# PROB_S7CAS_PHY.net
KiCad netlist of a schematic drawn in Altium Designer
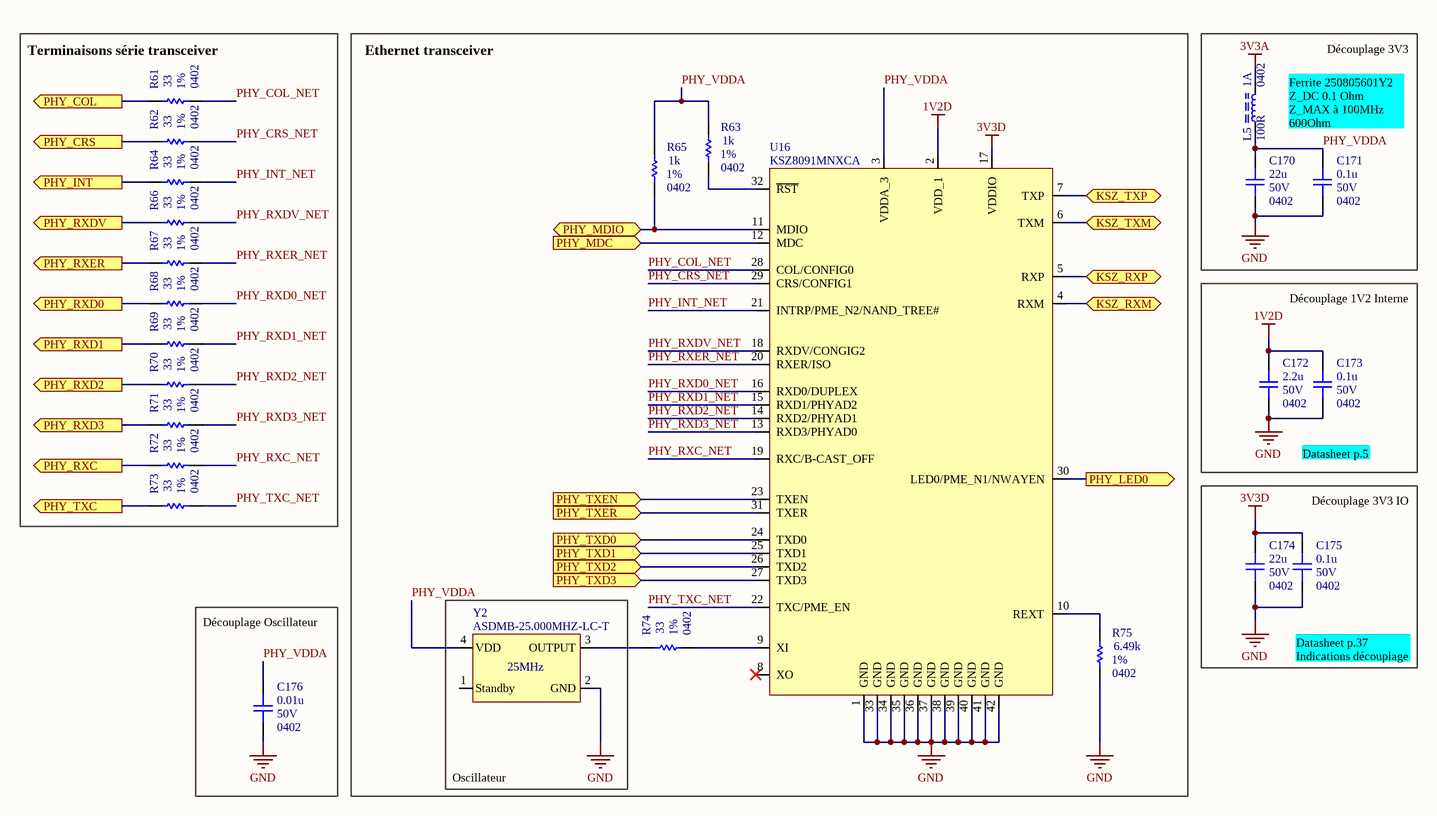
[diagram p0: PROB_S7CAS_PHY.SchDoc]

(export (version "E")
  (design (tool "Eeschema 10.0.6"))
  (components
    (comp (ref "C170")
      (value "22u")
      (footprint "CAP_0402")
      (description "CAP - 0402")
      (fields
        (field (name "VOLTAGE") "50V")
        (field (name "PACKAGE") "0402")
        (field (name "CREATEDBY") "Jonathan Bouchard")
      )
      (libsource (lib "S7CAS_LIB2021") (part "CAP - 0402"))
    )
    (comp (ref "C171")
      (value "0.1u")
      (footprint "CAP_0402")
      (description "CAP - 0402")
      (fields
        (field (name "VOLTAGE") "50V")
        (field (name "PACKAGE") "0402")
        (field (name "CREATEDBY") "Jonathan Bouchard")
      )
      (libsource (lib "S7CAS_LIB2021") (part "CAP - 0402"))
    )
    (comp (ref "C172")
      (value "2.2u")
      (footprint "CAP_0402")
      (description "CAP - 0402")
      (fields
        (field (name "VOLTAGE") "50V")
        (field (name "PACKAGE") "0402")
        (field (name "CREATEDBY") "Jonathan Bouchard")
      )
      (libsource (lib "S7CAS_LIB2021") (part "CAP - 0402"))
    )
    (comp (ref "C173")
      (value "0.1u")
      (footprint "CAP_0402")
      (description "CAP - 0402")
      (fields
        (field (name "VOLTAGE") "50V")
        (field (name "PACKAGE") "0402")
        (field (name "CREATEDBY") "Jonathan Bouchard")
      )
      (libsource (lib "S7CAS_LIB2021") (part "CAP - 0402"))
    )
    (comp (ref "C174")
      (value "22u")
      (footprint "CAP_0402")
      (description "CAP - 0402")
      (fields
        (field (name "VOLTAGE") "50V")
        (field (name "PACKAGE") "0402")
        (field (name "CREATEDBY") "Jonathan Bouchard")
      )
      (libsource (lib "S7CAS_LIB2021") (part "CAP - 0402"))
    )
    (comp (ref "C175")
      (value "0.1u")
      (footprint "CAP_0402")
      (description "CAP - 0402")
      (fields
        (field (name "VOLTAGE") "50V")
        (field (name "PACKAGE") "0402")
        (field (name "CREATEDBY") "Jonathan Bouchard")
      )
      (libsource (lib "S7CAS_LIB2021") (part "CAP - 0402"))
    )
    (comp (ref "C176")
      (value "0.01u")
      (footprint "CAP_0402")
      (description "CAP - 0402")
      (fields
        (field (name "VOLTAGE") "50V")
        (field (name "PACKAGE") "0402")
        (field (name "CREATEDBY") "Jonathan Bouchard")
      )
      (libsource (lib "S7CAS_LIB2021") (part "CAP - 0402"))
    )
    (comp (ref "L5")
      (value "100R")
      (footprint "FER_0402")
      (description "FER - 0402")
      (fields
        (field (name "CURRENT") "1A")
        (field (name "PACKAGE") "0402")
        (field (name "CREATEDBY") "Jonathan Bouchard")
      )
      (libsource (lib "S7CAS_LIB2021") (part "FER - 0402"))
    )
    (comp (ref "R61")
      (value "33")
      (footprint "RES_0402")
      (description "RES - 0402")
      (fields
        (field (name "VOLTAGE") "50V")
        (field (name "POWER") "1/16W")
        (field (name "PACKAGE") "0402")
        (field (name "PRECISION") "1%")
        (field (name "CREATEDBY") "Jonathan Bouchard")
      )
      (libsource (lib "S7CAS_LIB2021") (part "RES - 0402"))
    )
    (comp (ref "R62")
      (value "33")
      (footprint "RES_0402")
      (description "RES - 0402")
      (fields
        (field (name "VOLTAGE") "50V")
        (field (name "POWER") "1/16W")
        (field (name "PACKAGE") "0402")
        (field (name "PRECISION") "1%")
        (field (name "CREATEDBY") "Jonathan Bouchard")
      )
      (libsource (lib "S7CAS_LIB2021") (part "RES - 0402"))
    )
    (comp (ref "R63")
      (value "1k")
      (footprint "RES_0402")
      (description "RES - 0402")
      (fields
        (field (name "VOLTAGE") "50V")
        (field (name "POWER") "1/16W")
        (field (name "PACKAGE") "0402")
        (field (name "PRECISION") "1%")
        (field (name "CREATEDBY") "Jonathan Bouchard")
      )
      (libsource (lib "S7CAS_LIB2021") (part "RES - 0402"))
    )
    (comp (ref "R64")
      (value "33")
      (footprint "RES_0402")
      (description "RES - 0402")
      (fields
        (field (name "VOLTAGE") "50V")
        (field (name "POWER") "1/16W")
        (field (name "PACKAGE") "0402")
        (field (name "PRECISION") "1%")
        (field (name "CREATEDBY") "Jonathan Bouchard")
      )
      (libsource (lib "S7CAS_LIB2021") (part "RES - 0402"))
    )
    (comp (ref "R65")
      (value "1k")
      (footprint "RES_0402")
      (description "RES - 0402")
      (fields
        (field (name "VOLTAGE") "50V")
        (field (name "POWER") "1/16W")
        (field (name "PACKAGE") "0402")
        (field (name "PRECISION") "1%")
        (field (name "CREATEDBY") "Jonathan Bouchard")
      )
      (libsource (lib "S7CAS_LIB2021") (part "RES - 0402"))
    )
    (comp (ref "R66")
      (value "33")
      (footprint "RES_0402")
      (description "RES - 0402")
      (fields
        (field (name "VOLTAGE") "50V")
        (field (name "POWER") "1/16W")
        (field (name "PACKAGE") "0402")
        (field (name "PRECISION") "1%")
        (field (name "CREATEDBY") "Jonathan Bouchard")
      )
      (libsource (lib "S7CAS_LIB2021") (part "RES - 0402"))
    )
    (comp (ref "R67")
      (value "33")
      (footprint "RES_0402")
      (description "RES - 0402")
      (fields
        (field (name "VOLTAGE") "50V")
        (field (name "POWER") "1/16W")
        (field (name "PACKAGE") "0402")
        (field (name "PRECISION") "1%")
        (field (name "CREATEDBY") "Jonathan Bouchard")
      )
      (libsource (lib "S7CAS_LIB2021") (part "RES - 0402"))
    )
    (comp (ref "R68")
      (value "33")
      (footprint "RES_0402")
      (description "RES - 0402")
      (fields
        (field (name "VOLTAGE") "50V")
        (field (name "POWER") "1/16W")
        (field (name "PACKAGE") "0402")
        (field (name "PRECISION") "1%")
        (field (name "CREATEDBY") "Jonathan Bouchard")
      )
      (libsource (lib "S7CAS_LIB2021") (part "RES - 0402"))
    )
    (comp (ref "R69")
      (value "33")
      (footprint "RES_0402")
      (description "RES - 0402")
      (fields
        (field (name "VOLTAGE") "50V")
        (field (name "POWER") "1/16W")
        (field (name "PACKAGE") "0402")
        (field (name "PRECISION") "1%")
        (field (name "CREATEDBY") "Jonathan Bouchard")
      )
      (libsource (lib "S7CAS_LIB2021") (part "RES - 0402"))
    )
    (comp (ref "R70")
      (value "33")
      (footprint "RES_0402")
      (description "RES - 0402")
      (fields
        (field (name "VOLTAGE") "50V")
        (field (name "POWER") "1/16W")
        (field (name "PACKAGE") "0402")
        (field (name "PRECISION") "1%")
        (field (name "CREATEDBY") "Jonathan Bouchard")
      )
      (libsource (lib "S7CAS_LIB2021") (part "RES - 0402"))
    )
    (comp (ref "R71")
      (value "33")
      (footprint "RES_0402")
      (description "RES - 0402")
      (fields
        (field (name "VOLTAGE") "50V")
        (field (name "POWER") "1/16W")
        (field (name "PACKAGE") "0402")
        (field (name "PRECISION") "1%")
        (field (name "CREATEDBY") "Jonathan Bouchard")
      )
      (libsource (lib "S7CAS_LIB2021") (part "RES - 0402"))
    )
    (comp (ref "R72")
      (value "33")
      (footprint "RES_0402")
      (description "RES - 0402")
      (fields
        (field (name "VOLTAGE") "50V")
        (field (name "POWER") "1/16W")
        (field (name "PACKAGE") "0402")
        (field (name "PRECISION") "1%")
        (field (name "CREATEDBY") "Jonathan Bouchard")
      )
      (libsource (lib "S7CAS_LIB2021") (part "RES - 0402"))
    )
    (comp (ref "R73")
      (value "33")
      (footprint "RES_0402")
      (description "RES - 0402")
      (fields
        (field (name "VOLTAGE") "50V")
        (field (name "POWER") "1/16W")
        (field (name "PACKAGE") "0402")
        (field (name "PRECISION") "1%")
        (field (name "CREATEDBY") "Jonathan Bouchard")
      )
      (libsource (lib "S7CAS_LIB2021") (part "RES - 0402"))
    )
    (comp (ref "R74")
      (value "33")
      (footprint "RES_0402")
      (description "RES - 0402")
      (fields
        (field (name "VOLTAGE") "50V")
        (field (name "POWER") "1/16W")
        (field (name "PACKAGE") "0402")
        (field (name "PRECISION") "1%")
        (field (name "CREATEDBY") "Jonathan Bouchard")
      )
      (libsource (lib "S7CAS_LIB2021") (part "RES - 0402"))
    )
    (comp (ref "R75")
      (value "6.49k")
      (footprint "RES_0402")
      (description "RES - 0402")
      (fields
        (field (name "VOLTAGE") "50V")
        (field (name "POWER") "1/16W")
        (field (name "PACKAGE") "0402")
        (field (name "PRECISION") "1%")
        (field (name "CREATEDBY") "Jonathan Bouchard")
      )
      (libsource (lib "S7CAS_LIB2021") (part "RES - 0402"))
    )
    (comp (ref "U16")
      (value "KSZ8091MNXCA")
      (footprint "COM_ETH_PHY_KSZ8091MNXCA")
      (description "COM - ETHERNET PHY 10/100 - QFN-32")
      (fields
        (field (name "VOLTAGE") "1.8V, 2.5V, 3.3V")
        (field (name "MFG") "Micrel")
        (field (name "CREATEDBY") "Jonathan Bouchard")
      )
      (libsource (lib "S7CAS_LIB2021") (part "COM_ETH_PHY_KSZ8091MNXCA"))
    )
    (comp (ref "Y2")
      (value "ASDMB-25.000MHZ-LC-T")
      (footprint "OSC_ASDMB-25.000MHZ-LC-T")
      (description "OSC - 25MHz XO (Standard) LVCMOS - 4-SMD, No Lead")
      (fields
        (field (name "TOLERANCE") "±50ppm")
        (field (name "CREATEDBY/DATE") "Joël Lemay 2019-03-29")
        (field (name "VERIFIEDBY") "C. Paulin - 29 mai 2019")
      )
      (libsource (lib "S7CAS_LIB2021") (part "OSC_ASDMB-25.000MHZ-LC-T"))
    )
  )
  (nets
    (net (code "1") (name "/KSZ_RXM") (class "Default")
      (node (ref "U16") (pin "4") (pinfunction "RXM_4") (pintype "passive"))
    )
    (net (code "2") (name "/KSZ_RXP") (class "Default")
      (node (ref "U16") (pin "5") (pinfunction "RXP_5") (pintype "passive"))
    )
    (net (code "3") (name "/KSZ_TXM") (class "Default")
      (node (ref "U16") (pin "6") (pinfunction "TXM_6") (pintype "passive"))
    )
    (net (code "4") (name "/KSZ_TXP") (class "Default")
      (node (ref "U16") (pin "7") (pinfunction "TXP_7") (pintype "passive"))
    )
    (net (code "5") (name "/PHY_COL") (class "Default")
      (node (ref "R61") (pin "2") (pinfunction "2_2") (pintype "passive"))
    )
    (net (code "6") (name "/PHY_COL_NET") (class "Default")
      (node (ref "R61") (pin "1") (pinfunction "1_1") (pintype "passive"))
      (node (ref "U16") (pin "28") (pinfunction "COL/CONFIG0_28") (pintype "passive"))
    )
    (net (code "7") (name "/PHY_CRS") (class "Default")
      (node (ref "R62") (pin "2") (pinfunction "2_2") (pintype "passive"))
    )
    (net (code "8") (name "/PHY_CRS_NET") (class "Default")
      (node (ref "R62") (pin "1") (pinfunction "1_1") (pintype "passive"))
      (node (ref "U16") (pin "29") (pinfunction "CRS/CONFIG1_29") (pintype "passive"))
    )
    (net (code "9") (name "/PHY_INT") (class "Default")
      (node (ref "R64") (pin "2") (pinfunction "2_2") (pintype "passive"))
    )
    (net (code "10") (name "/PHY_INT_NET") (class "Default")
      (node (ref "R64") (pin "1") (pinfunction "1_1") (pintype "passive"))
      (node (ref "U16") (pin "21") (pinfunction "INTRP/PME_N2/NAND_TREE#_21") (pintype "passive"))
    )
    (net (code "11") (name "/PHY_LED0") (class "Default")
      (node (ref "U16") (pin "30") (pinfunction "LED0/PME_N1/NWAYEN_30") (pintype "passive"))
    )
    (net (code "12") (name "/PHY_MDC") (class "Default")
      (node (ref "U16") (pin "12") (pinfunction "MDC_12") (pintype "passive"))
    )
    (net (code "13") (name "/PHY_MDIO") (class "Default")
      (node (ref "R65") (pin "1") (pinfunction "1_1") (pintype "passive"))
      (node (ref "U16") (pin "11") (pinfunction "MDIO_11") (pintype "passive"))
    )
    (net (code "14") (name "/PHY_RXC") (class "Default")
      (node (ref "R72") (pin "2") (pinfunction "2_2") (pintype "passive"))
    )
    (net (code "15") (name "/PHY_RXC_NET") (class "Default")
      (node (ref "R72") (pin "1") (pinfunction "1_1") (pintype "passive"))
      (node (ref "U16") (pin "19") (pinfunction "RXC/B-CAST_OFF_19") (pintype "passive"))
    )
    (net (code "16") (name "/PHY_RXD0") (class "Default")
      (node (ref "R68") (pin "2") (pinfunction "2_2") (pintype "passive"))
    )
    (net (code "17") (name "/PHY_RXD0_NET") (class "Default")
      (node (ref "R68") (pin "1") (pinfunction "1_1") (pintype "passive"))
      (node (ref "U16") (pin "16") (pinfunction "RXD0/DUPLEX_16") (pintype "passive"))
    )
    (net (code "18") (name "/PHY_RXD1") (class "Default")
      (node (ref "R69") (pin "2") (pinfunction "2_2") (pintype "passive"))
    )
    (net (code "19") (name "/PHY_RXD1_NET") (class "Default")
      (node (ref "R69") (pin "1") (pinfunction "1_1") (pintype "passive"))
      (node (ref "U16") (pin "15") (pinfunction "RXD1/PHYAD2_15") (pintype "passive"))
    )
    (net (code "20") (name "/PHY_RXD2") (class "Default")
      (node (ref "R70") (pin "2") (pinfunction "2_2") (pintype "passive"))
    )
    (net (code "21") (name "/PHY_RXD2_NET") (class "Default")
      (node (ref "R70") (pin "1") (pinfunction "1_1") (pintype "passive"))
      (node (ref "U16") (pin "14") (pinfunction "RXD2/PHYAD1_14") (pintype "passive"))
    )
    (net (code "22") (name "/PHY_RXD3") (class "Default")
      (node (ref "R71") (pin "2") (pinfunction "2_2") (pintype "passive"))
    )
    (net (code "23") (name "/PHY_RXD3_NET") (class "Default")
      (node (ref "R71") (pin "1") (pinfunction "1_1") (pintype "passive"))
      (node (ref "U16") (pin "13") (pinfunction "RXD3/PHYAD0_13") (pintype "passive"))
    )
    (net (code "24") (name "/PHY_RXDV") (class "Default")
      (node (ref "R66") (pin "2") (pinfunction "2_2") (pintype "passive"))
    )
    (net (code "25") (name "/PHY_RXDV_NET") (class "Default")
      (node (ref "R66") (pin "1") (pinfunction "1_1") (pintype "passive"))
      (node (ref "U16") (pin "18") (pinfunction "RXDV/CONGIG2_18") (pintype "passive"))
    )
    (net (code "26") (name "/PHY_RXER") (class "Default")
      (node (ref "R67") (pin "2") (pinfunction "2_2") (pintype "passive"))
    )
    (net (code "27") (name "/PHY_RXER_NET") (class "Default")
      (node (ref "R67") (pin "1") (pinfunction "1_1") (pintype "passive"))
      (node (ref "U16") (pin "20") (pinfunction "RXER/ISO_20") (pintype "passive"))
    )
    (net (code "28") (name "/PHY_TXC") (class "Default")
      (node (ref "R73") (pin "2") (pinfunction "2_2") (pintype "passive"))
    )
    (net (code "29") (name "/PHY_TXC_NET") (class "Default")
      (node (ref "R73") (pin "1") (pinfunction "1_1") (pintype "passive"))
      (node (ref "U16") (pin "22") (pinfunction "TXC/PME_EN_22") (pintype "passive"))
    )
    (net (code "30") (name "/PHY_TXD0") (class "Default")
      (node (ref "U16") (pin "24") (pinfunction "TXD0_24") (pintype "passive"))
    )
    (net (code "31") (name "/PHY_TXD1") (class "Default")
      (node (ref "U16") (pin "25") (pinfunction "TXD1_25") (pintype "passive"))
    )
    (net (code "32") (name "/PHY_TXD2") (class "Default")
      (node (ref "U16") (pin "26") (pinfunction "TXD2_26") (pintype "passive"))
    )
    (net (code "33") (name "/PHY_TXD3") (class "Default")
      (node (ref "U16") (pin "27") (pinfunction "TXD3_27") (pintype "passive"))
    )
    (net (code "34") (name "/PHY_TXEN") (class "Default")
      (node (ref "U16") (pin "23") (pinfunction "TXEN_23") (pintype "passive"))
    )
    (net (code "35") (name "/PHY_TXER") (class "Default")
      (node (ref "U16") (pin "31") (pinfunction "TXER_31") (pintype "passive"))
    )
    (net (code "36") (name "/PHY_VDDA") (class "Default")
      (node (ref "C170") (pin "2") (pinfunction "2_2") (pintype "passive"))
      (node (ref "C171") (pin "2") (pinfunction "2_2") (pintype "passive"))
      (node (ref "C176") (pin "2") (pinfunction "2_2") (pintype "passive"))
      (node (ref "L5") (pin "2") (pinfunction "2_2") (pintype "passive"))
      (node (ref "R63") (pin "2") (pinfunction "2_2") (pintype "passive"))
      (node (ref "R65") (pin "2") (pinfunction "2_2") (pintype "passive"))
      (node (ref "U16") (pin "3") (pinfunction "VDDA_3_3") (pintype "power_in"))
      (node (ref "Y2") (pin "4") (pinfunction "VDD_4") (pintype "passive"))
    )
    (net (code "37") (name "1V2D") (class "Default")
      (node (ref "C172") (pin "2") (pinfunction "2_2") (pintype "passive"))
      (node (ref "C173") (pin "2") (pinfunction "2_2") (pintype "passive"))
      (node (ref "U16") (pin "2") (pinfunction "VDD_1_2") (pintype "power_in"))
    )
    (net (code "38") (name "3V3A") (class "Default")
      (node (ref "L5") (pin "1") (pinfunction "1_1") (pintype "passive"))
    )
    (net (code "39") (name "3V3D") (class "Default")
      (node (ref "C174") (pin "2") (pinfunction "2_2") (pintype "passive"))
      (node (ref "C175") (pin "2") (pinfunction "2_2") (pintype "passive"))
      (node (ref "U16") (pin "17") (pinfunction "VDDIO_17") (pintype "power_in"))
    )
    (net (code "40") (name "GND") (class "Default")
      (node (ref "C170") (pin "1") (pinfunction "1_1") (pintype "passive"))
      (node (ref "C171") (pin "1") (pinfunction "1_1") (pintype "passive"))
      (node (ref "C172") (pin "1") (pinfunction "1_1") (pintype "passive"))
      (node (ref "C173") (pin "1") (pinfunction "1_1") (pintype "passive"))
      (node (ref "C174") (pin "1") (pinfunction "1_1") (pintype "passive"))
      (node (ref "C175") (pin "1") (pinfunction "1_1") (pintype "passive"))
      (node (ref "C176") (pin "1") (pinfunction "1_1") (pintype "passive"))
      (node (ref "R75") (pin "1") (pinfunction "1_1") (pintype "passive"))
      (node (ref "U16") (pin "1") (pinfunction "GND_1") (pintype "passive"))
      (node (ref "U16") (pin "33") (pinfunction "GND_33") (pintype "passive"))
      (node (ref "U16") (pin "34") (pinfunction "GND_34") (pintype "passive"))
      (node (ref "U16") (pin "35") (pinfunction "GND_35") (pintype "passive"))
      (node (ref "U16") (pin "36") (pinfunction "GND_36") (pintype "passive"))
      (node (ref "U16") (pin "37") (pinfunction "GND_37") (pintype "passive"))
      (node (ref "U16") (pin "38") (pinfunction "GND_38") (pintype "passive"))
      (node (ref "U16") (pin "39") (pinfunction "GND_39") (pintype "passive"))
      (node (ref "U16") (pin "40") (pinfunction "GND_40") (pintype "passive"))
      (node (ref "U16") (pin "41") (pinfunction "GND_41") (pintype "passive"))
      (node (ref "U16") (pin "42") (pinfunction "GND_42") (pintype "passive"))
      (node (ref "Y2") (pin "2") (pinfunction "GND_2") (pintype "passive"))
    )
    (net (code "41") (name "Net-(U16-REXT)") (class "Default")
      (node (ref "R75") (pin "2") (pinfunction "2_2") (pintype "passive"))
      (node (ref "U16") (pin "10") (pinfunction "REXT_10") (pintype "passive"))
    )
    (net (code "42") (name "Net-(U16-RST)") (class "Default")
      (node (ref "R63") (pin "1") (pinfunction "1_1") (pintype "passive"))
      (node (ref "U16") (pin "32") (pinfunction "RST_32") (pintype "passive"))
    )
    (net (code "43") (name "Net-(U16-XI)") (class "Default")
      (node (ref "R74") (pin "1") (pinfunction "1_1") (pintype "passive"))
      (node (ref "U16") (pin "9") (pinfunction "XI_9") (pintype "passive"))
    )
    (net (code "44") (name "Net-(Y2-OUTPUT)") (class "Default")
      (node (ref "R74") (pin "2") (pinfunction "2_2") (pintype "passive"))
      (node (ref "Y2") (pin "3") (pinfunction "OUTPUT_3") (pintype "passive"))
    )
    (net (code "45") (name "unconnected-(U16-XO-Pad8)") (class "Default")
      (node (ref "U16") (pin "8") (pinfunction "XO_8") (pintype "passive+no_connect"))
    )
    (net (code "46") (name "unconnected-(Y2-Standby-Pad1)") (class "Default")
      (node (ref "Y2") (pin "1") (pinfunction "Standby_1") (pintype "passive"))
    )
  )
)
